# 5_Periperals.net
KiCad netlist of a schematic drawn in Altium Designer
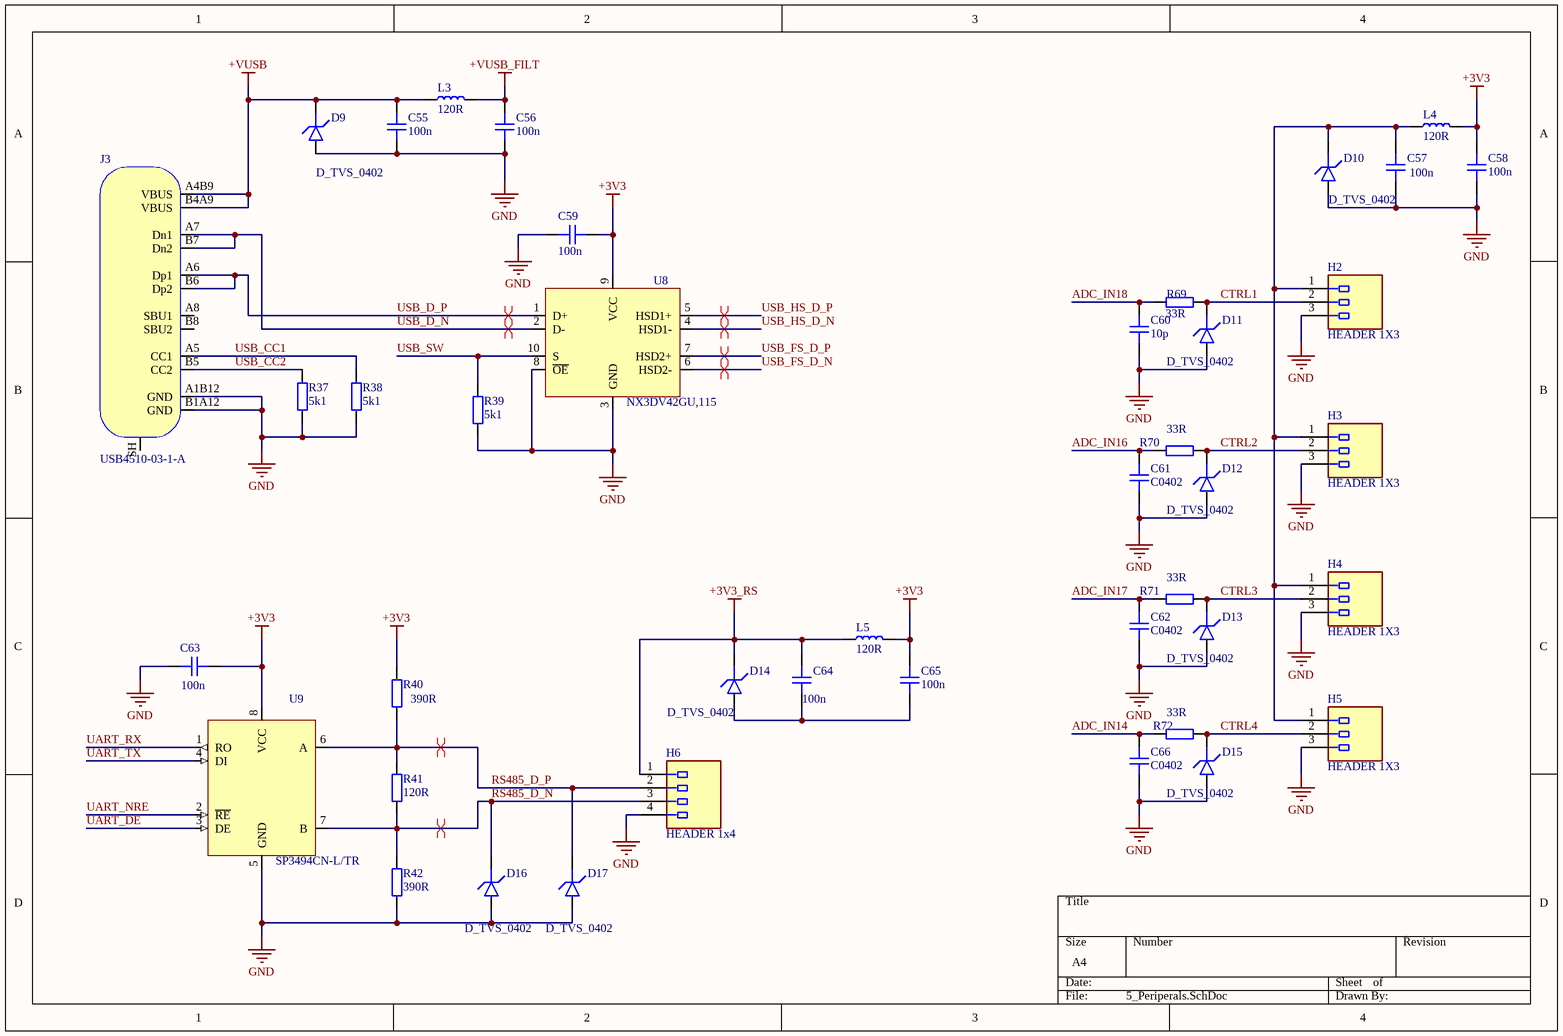
[diagram p0: 5_Periperals.SchDoc]

(export (version "E")
  (design (tool "Eeschema 10.0.6"))
  (components
    (comp (ref "C55")
      (value "100n")
      (footprint "CAP_0402")
      (description "Capacitor SMD 0402")
      (libsource (lib "Schematic-Lib-PhilsLab") (part "CAP_0402"))
    )
    (comp (ref "C56")
      (value "100n")
      (footprint "CAP_0402")
      (description "Capacitor SMD 0402")
      (libsource (lib "Schematic-Lib-PhilsLab") (part "CAP_0402"))
    )
    (comp (ref "C57")
      (value "100n")
      (footprint "CAP_0402")
      (description "Capacitor SMD 0402")
      (libsource (lib "Schematic-Lib-PhilsLab") (part "CAP_0402"))
    )
    (comp (ref "C58")
      (value "100n")
      (footprint "CAP_0402")
      (description "Capacitor SMD 0402")
      (libsource (lib "Schematic-Lib-PhilsLab") (part "CAP_0402"))
    )
    (comp (ref "C59")
      (value "100n")
      (footprint "CAP_0402")
      (description "Capacitor SMD 0402")
      (libsource (lib "Schematic-Lib-PhilsLab") (part "CAP_0402"))
    )
    (comp (ref "C60")
      (value "10p")
      (footprint "CAP_0402")
      (description "Capacitor SMD 0402")
      (libsource (lib "Schematic-Lib-PhilsLab") (part "CAP_0402"))
    )
    (comp (ref "C61")
      (value "C0402")
      (footprint "CAP_0402")
      (description "Capacitor SMD 0402")
      (libsource (lib "Schematic-Lib-PhilsLab") (part "CAP_0402"))
    )
    (comp (ref "C62")
      (value "C0402")
      (footprint "CAP_0402")
      (description "Capacitor SMD 0402")
      (libsource (lib "Schematic-Lib-PhilsLab") (part "CAP_0402"))
    )
    (comp (ref "C63")
      (value "100n")
      (footprint "CAP_0402")
      (description "Capacitor SMD 0402")
      (libsource (lib "Schematic-Lib-PhilsLab") (part "CAP_0402"))
    )
    (comp (ref "C64")
      (value "100n")
      (footprint "CAP_0402")
      (description "Capacitor SMD 0402")
      (libsource (lib "Schematic-Lib-PhilsLab") (part "CAP_0402"))
    )
    (comp (ref "C65")
      (value "100n")
      (footprint "CAP_0402")
      (description "Capacitor SMD 0402")
      (libsource (lib "Schematic-Lib-PhilsLab") (part "CAP_0402"))
    )
    (comp (ref "C66")
      (value "C0402")
      (footprint "CAP_0402")
      (description "Capacitor SMD 0402")
      (libsource (lib "Schematic-Lib-PhilsLab") (part "CAP_0402"))
    )
    (comp (ref "D9")
      (value "D_TVS_0402")
      (footprint "D_0402")
      (description "Diode TVS / ESD 0402")
      (libsource (lib "Schematic-Lib-PhilsLab") (part "D_TVS_0402"))
    )
    (comp (ref "D10")
      (value "D_TVS_0402")
      (footprint "D_0402")
      (description "Diode TVS / ESD 0402")
      (libsource (lib "Schematic-Lib-PhilsLab") (part "D_TVS_0402"))
    )
    (comp (ref "D11")
      (value "D_TVS_0402")
      (footprint "D_0402")
      (description "Diode TVS / ESD 0402")
      (libsource (lib "Schematic-Lib-PhilsLab") (part "D_TVS_0402"))
    )
    (comp (ref "D12")
      (value "D_TVS_0402")
      (footprint "D_0402")
      (description "Diode TVS / ESD 0402")
      (libsource (lib "Schematic-Lib-PhilsLab") (part "D_TVS_0402"))
    )
    (comp (ref "D13")
      (value "D_TVS_0402")
      (footprint "D_0402")
      (description "Diode TVS / ESD 0402")
      (libsource (lib "Schematic-Lib-PhilsLab") (part "D_TVS_0402"))
    )
    (comp (ref "D14")
      (value "D_TVS_0402")
      (footprint "D_0402")
      (description "Diode TVS / ESD 0402")
      (libsource (lib "Schematic-Lib-PhilsLab") (part "D_TVS_0402"))
    )
    (comp (ref "D15")
      (value "D_TVS_0402")
      (footprint "D_0402")
      (description "Diode TVS / ESD 0402")
      (libsource (lib "Schematic-Lib-PhilsLab") (part "D_TVS_0402"))
    )
    (comp (ref "D16")
      (value "D_TVS_0402")
      (footprint "D_0402")
      (description "Diode TVS / ESD 0402")
      (libsource (lib "Schematic-Lib-PhilsLab") (part "D_TVS_0402"))
    )
    (comp (ref "D17")
      (value "D_TVS_0402")
      (footprint "D_0402")
      (description "Diode TVS / ESD 0402")
      (libsource (lib "Schematic-Lib-PhilsLab") (part "D_TVS_0402"))
    )
    (comp (ref "H2")
      (value "HEADER 1X3")
      (footprint "053048-0310")
      (libsource (lib "SCHLib") (part "053048-0310"))
    )
    (comp (ref "H3")
      (value "HEADER 1X3")
      (footprint "053048-0310")
      (libsource (lib "SCHLib") (part "053048-0310"))
    )
    (comp (ref "H4")
      (value "HEADER 1X3")
      (footprint "053048-0310")
      (libsource (lib "SCHLib") (part "053048-0310"))
    )
    (comp (ref "H5")
      (value "HEADER 1X3")
      (footprint "053048-0310")
      (libsource (lib "SCHLib") (part "053048-0310"))
    )
    (comp (ref "H6")
      (value "HEADER 1x4")
      (footprint "053048-0410")
      (libsource (lib "SCHLib") (part "053048-0410"))
    )
    (comp (ref "J3")
      (value "USB4510-03-1-A")
      (footprint "USB4510-03-1-A")
      (description "USB Connector Type C SMT Mid-Mount 16 Pin")
      (fields (field (name "MANUFACTURER") "GCT"))
      (libsource (lib "Schematic-Lib-PhilsLab") (part "USB4510-03-1-A"))
    )
    (comp (ref "L3")
      (value "120R")
      (footprint "IND_0402")
      (description "Inductor SMD 0402")
      (libsource (lib "Schematic-Lib-PhilsLab") (part "IND_0402"))
    )
    (comp (ref "L4")
      (value "120R")
      (footprint "IND_0402")
      (description "Inductor SMD 0402")
      (libsource (lib "Schematic-Lib-PhilsLab") (part "IND_0402"))
    )
    (comp (ref "L5")
      (value "120R")
      (footprint "IND_0402")
      (description "Inductor SMD 0402")
      (libsource (lib "Schematic-Lib-PhilsLab") (part "IND_0402"))
    )
    (comp (ref "R37")
      (value "5k1")
      (footprint "RES_0402")
      (description "Resistor SMD 0402")
      (libsource (lib "Schematic-Lib-PhilsLab") (part "RES_0402"))
    )
    (comp (ref "R38")
      (value "5k1")
      (footprint "RES_0402")
      (description "Resistor SMD 0402")
      (libsource (lib "Schematic-Lib-PhilsLab") (part "RES_0402"))
    )
    (comp (ref "R39")
      (value "5k1")
      (footprint "RES_0402")
      (description "Resistor SMD 0402")
      (libsource (lib "Schematic-Lib-PhilsLab") (part "RES_0402"))
    )
    (comp (ref "R40")
      (value "390R")
      (footprint "RES_0402")
      (description "Resistor SMD 0402")
      (libsource (lib "Schematic-Lib-PhilsLab") (part "RES_0402"))
    )
    (comp (ref "R41")
      (value "120R")
      (footprint "RES_0402")
      (description "Resistor SMD 0402")
      (libsource (lib "Schematic-Lib-PhilsLab") (part "RES_0402"))
    )
    (comp (ref "R42")
      (value "390R")
      (footprint "RES_0402")
      (description "Resistor SMD 0402")
      (libsource (lib "Schematic-Lib-PhilsLab") (part "RES_0402"))
    )
    (comp (ref "R69")
      (value "33R")
      (footprint "RES_0402")
      (description "Resistor SMD 0402")
      (libsource (lib "Schematic-Lib-PhilsLab") (part "RES_0402"))
    )
    (comp (ref "R70")
      (value "33R")
      (footprint "RES_0402")
      (description "Resistor SMD 0402")
      (libsource (lib "Schematic-Lib-PhilsLab") (part "RES_0402"))
    )
    (comp (ref "R71")
      (value "33R")
      (footprint "RES_0402")
      (description "Resistor SMD 0402")
      (libsource (lib "Schematic-Lib-PhilsLab") (part "RES_0402"))
    )
    (comp (ref "R72")
      (value "33R")
      (footprint "RES_0402")
      (description "Resistor SMD 0402")
      (libsource (lib "Schematic-Lib-PhilsLab") (part "RES_0402"))
    )
    (comp (ref "U8")
      (value "NX3DV42GU,115")
      (footprint "XQFN-10_SOT1160-1")
      (description "USB2.0 HS DPDT Switch")
      (fields (field (name "MANUFACTURER") "NXP Semiconductors"))
      (libsource (lib "Schematic-Lib-PhilsLab") (part "NX3DV42GU,115"))
    )
    (comp (ref "U9")
      (value "SP3494CN-L/TR")
      (footprint "SOIC-8")
      (description "3.3V Low Power RS-485 / RS-422 Transceiver SOIC-8")
      (fields (field (name "MANUFACTURER") "MaxLinear"))
      (libsource (lib "Schematic-Lib-PhilsLab") (part "SP3494CN-L/TR"))
    )
  )
  (nets
    (net (code "1") (name "+3V3") (class "Default")
      (node (ref "C58") (pin "1") (pinfunction "1_1") (pintype "passive"))
      (node (ref "C59") (pin "1") (pinfunction "1_1") (pintype "passive"))
      (node (ref "C63") (pin "2") (pinfunction "2_2") (pintype "passive"))
      (node (ref "C65") (pin "1") (pinfunction "1_1") (pintype "passive"))
      (node (ref "L4") (pin "2") (pinfunction "2_2") (pintype "passive"))
      (node (ref "L5") (pin "2") (pinfunction "2_2") (pintype "passive"))
      (node (ref "R40") (pin "2") (pinfunction "2_2") (pintype "passive"))
      (node (ref "U8") (pin "9") (pinfunction "VCC_9") (pintype "passive"))
      (node (ref "U9") (pin "8") (pinfunction "VCC_8") (pintype "power_in"))
    )
    (net (code "2") (name "+3V3_RS") (class "Default")
      (node (ref "C64") (pin "1") (pinfunction "1_1") (pintype "passive"))
      (node (ref "D14") (pin "K") (pinfunction "K_K") (pintype "passive"))
      (node (ref "H6") (pin "1") (pinfunction "1_1") (pintype "passive"))
      (node (ref "L5") (pin "1") (pinfunction "1_1") (pintype "passive"))
    )
    (net (code "3") (name "+VUSB") (class "Default")
      (node (ref "C55") (pin "1") (pinfunction "1_1") (pintype "passive"))
      (node (ref "D9") (pin "K") (pinfunction "K_K") (pintype "passive"))
      (node (ref "J3") (pin "A4B9") (pinfunction "VBUS_A4B9") (pintype "passive"))
      (node (ref "J3") (pin "B4A9") (pinfunction "VBUS_B4A9") (pintype "passive"))
      (node (ref "L3") (pin "1") (pinfunction "1_1") (pintype "passive"))
    )
    (net (code "4") (name "+VUSB_FILT") (class "Default")
      (node (ref "C56") (pin "1") (pinfunction "1_1") (pintype "passive"))
      (node (ref "L3") (pin "2") (pinfunction "2_2") (pintype "passive"))
    )
    (net (code "5") (name "/ADC_IN14") (class "Default")
      (node (ref "C66") (pin "1") (pinfunction "1_1") (pintype "passive"))
      (node (ref "R72") (pin "1") (pinfunction "1_1") (pintype "passive"))
    )
    (net (code "6") (name "/ADC_IN16") (class "Default")
      (node (ref "C61") (pin "1") (pinfunction "1_1") (pintype "passive"))
      (node (ref "R70") (pin "1") (pinfunction "1_1") (pintype "passive"))
    )
    (net (code "7") (name "/ADC_IN17") (class "Default")
      (node (ref "C62") (pin "1") (pinfunction "1_1") (pintype "passive"))
      (node (ref "R71") (pin "1") (pinfunction "1_1") (pintype "passive"))
    )
    (net (code "8") (name "/ADC_IN18") (class "Default")
      (node (ref "C60") (pin "1") (pinfunction "1_1") (pintype "passive"))
      (node (ref "R69") (pin "1") (pinfunction "1_1") (pintype "passive"))
    )
    (net (code "9") (name "/CTRL1") (class "Default")
      (node (ref "D11") (pin "K") (pinfunction "K_K") (pintype "passive"))
      (node (ref "H2") (pin "2") (pinfunction "2_2") (pintype "passive"))
      (node (ref "R69") (pin "2") (pinfunction "2_2") (pintype "passive"))
    )
    (net (code "10") (name "/CTRL2") (class "Default")
      (node (ref "D12") (pin "K") (pinfunction "K_K") (pintype "passive"))
      (node (ref "H3") (pin "2") (pinfunction "2_2") (pintype "passive"))
      (node (ref "R70") (pin "2") (pinfunction "2_2") (pintype "passive"))
    )
    (net (code "11") (name "/CTRL3") (class "Default")
      (node (ref "D13") (pin "K") (pinfunction "K_K") (pintype "passive"))
      (node (ref "H4") (pin "2") (pinfunction "2_2") (pintype "passive"))
      (node (ref "R71") (pin "2") (pinfunction "2_2") (pintype "passive"))
    )
    (net (code "12") (name "/CTRL4") (class "Default")
      (node (ref "D15") (pin "K") (pinfunction "K_K") (pintype "passive"))
      (node (ref "H5") (pin "2") (pinfunction "2_2") (pintype "passive"))
      (node (ref "R72") (pin "2") (pinfunction "2_2") (pintype "passive"))
    )
    (net (code "13") (name "/RS485_D_N") (class "Default")
      (node (ref "D16") (pin "K") (pinfunction "K_K") (pintype "passive"))
      (node (ref "H6") (pin "3") (pinfunction "3_3") (pintype "passive"))
      (node (ref "R41") (pin "1") (pinfunction "1_1") (pintype "passive"))
      (node (ref "R42") (pin "2") (pinfunction "2_2") (pintype "passive"))
      (node (ref "U9") (pin "7") (pinfunction "B_7") (pintype "bidirectional"))
    )
    (net (code "14") (name "/RS485_D_P") (class "Default")
      (node (ref "D17") (pin "K") (pinfunction "K_K") (pintype "passive"))
      (node (ref "H6") (pin "2") (pinfunction "2_2") (pintype "passive"))
      (node (ref "R40") (pin "1") (pinfunction "1_1") (pintype "passive"))
      (node (ref "R41") (pin "2") (pinfunction "2_2") (pintype "passive"))
      (node (ref "U9") (pin "6") (pinfunction "A_6") (pintype "bidirectional"))
    )
    (net (code "15") (name "/UART_DE") (class "Default")
      (node (ref "U9") (pin "3") (pinfunction "DE_3") (pintype "input"))
    )
    (net (code "16") (name "/UART_NRE") (class "Default")
      (node (ref "U9") (pin "2") (pinfunction "~{RE}_2") (pintype "input"))
    )
    (net (code "17") (name "/UART_RX") (class "Default")
      (node (ref "U9") (pin "1") (pinfunction "RO_1") (pintype "output"))
    )
    (net (code "18") (name "/UART_TX") (class "Default")
      (node (ref "U9") (pin "4") (pinfunction "DI_4") (pintype "input"))
    )
    (net (code "19") (name "/USB_CC1") (class "Default")
      (node (ref "J3") (pin "A5") (pinfunction "CC1_A5") (pintype "passive"))
      (node (ref "R38") (pin "2") (pinfunction "2_2") (pintype "passive"))
    )
    (net (code "20") (name "/USB_CC2") (class "Default")
      (node (ref "J3") (pin "B5") (pinfunction "CC2_B5") (pintype "passive"))
      (node (ref "R37") (pin "2") (pinfunction "2_2") (pintype "passive"))
    )
    (net (code "21") (name "/USB_D_N") (class "Default")
      (node (ref "J3") (pin "A7") (pinfunction "Dn1_A7") (pintype "passive"))
      (node (ref "J3") (pin "B7") (pinfunction "Dn2_B7") (pintype "passive"))
      (node (ref "U8") (pin "2") (pinfunction "D-_2") (pintype "passive"))
    )
    (net (code "22") (name "/USB_D_P") (class "Default")
      (node (ref "J3") (pin "A6") (pinfunction "Dp1_A6") (pintype "passive"))
      (node (ref "J3") (pin "B6") (pinfunction "Dp2_B6") (pintype "passive"))
      (node (ref "U8") (pin "1") (pinfunction "D+_1") (pintype "passive"))
    )
    (net (code "23") (name "/USB_FS_D_N") (class "Default")
      (node (ref "U8") (pin "6") (pinfunction "HSD2-_6") (pintype "passive"))
    )
    (net (code "24") (name "/USB_FS_D_P") (class "Default")
      (node (ref "U8") (pin "7") (pinfunction "HSD2+_7") (pintype "passive"))
    )
    (net (code "25") (name "/USB_HS_D_N") (class "Default")
      (node (ref "U8") (pin "4") (pinfunction "HSD1-_4") (pintype "passive"))
    )
    (net (code "26") (name "/USB_HS_D_P") (class "Default")
      (node (ref "U8") (pin "5") (pinfunction "HSD1+_5") (pintype "passive"))
    )
    (net (code "27") (name "/USB_SW") (class "Default")
      (node (ref "R39") (pin "2") (pinfunction "2_2") (pintype "passive"))
      (node (ref "U8") (pin "10") (pinfunction "S_10") (pintype "passive"))
    )
    (net (code "28") (name "GND") (class "Default")
      (node (ref "C55") (pin "2") (pinfunction "2_2") (pintype "passive"))
      (node (ref "C56") (pin "2") (pinfunction "2_2") (pintype "passive"))
      (node (ref "C57") (pin "2") (pinfunction "2_2") (pintype "passive"))
      (node (ref "C58") (pin "2") (pinfunction "2_2") (pintype "passive"))
      (node (ref "C59") (pin "2") (pinfunction "2_2") (pintype "passive"))
      (node (ref "C60") (pin "2") (pinfunction "2_2") (pintype "passive"))
      (node (ref "C61") (pin "2") (pinfunction "2_2") (pintype "passive"))
      (node (ref "C62") (pin "2") (pinfunction "2_2") (pintype "passive"))
      (node (ref "C63") (pin "1") (pinfunction "1_1") (pintype "passive"))
      (node (ref "C66") (pin "2") (pinfunction "2_2") (pintype "passive"))
      (node (ref "D10") (pin "A") (pinfunction "A_A") (pintype "passive"))
      (node (ref "D11") (pin "A") (pinfunction "A_A") (pintype "passive"))
      (node (ref "D12") (pin "A") (pinfunction "A_A") (pintype "passive"))
      (node (ref "D13") (pin "A") (pinfunction "A_A") (pintype "passive"))
      (node (ref "D15") (pin "A") (pinfunction "A_A") (pintype "passive"))
      (node (ref "D16") (pin "A") (pinfunction "A_A") (pintype "passive"))
      (node (ref "D17") (pin "A") (pinfunction "A_A") (pintype "passive"))
      (node (ref "D9") (pin "A") (pinfunction "A_A") (pintype "passive"))
      (node (ref "H2") (pin "3") (pinfunction "3_3") (pintype "passive"))
      (node (ref "H3") (pin "3") (pinfunction "3_3") (pintype "passive"))
      (node (ref "H4") (pin "3") (pinfunction "3_3") (pintype "passive"))
      (node (ref "H5") (pin "3") (pinfunction "3_3") (pintype "passive"))
      (node (ref "H6") (pin "4") (pinfunction "4_4") (pintype "passive"))
      (node (ref "J3") (pin "A1B12") (pinfunction "GND_A1B12") (pintype "passive"))
      (node (ref "J3") (pin "B1A12") (pinfunction "GND_B1A12") (pintype "passive"))
      (node (ref "R37") (pin "1") (pinfunction "1_1") (pintype "passive"))
      (node (ref "R38") (pin "1") (pinfunction "1_1") (pintype "passive"))
      (node (ref "R39") (pin "1") (pinfunction "1_1") (pintype "passive"))
      (node (ref "R42") (pin "1") (pinfunction "1_1") (pintype "passive"))
      (node (ref "U8") (pin "3") (pinfunction "GND_3") (pintype "passive"))
      (node (ref "U8") (pin "8") (pinfunction "~{OE}_8") (pintype "passive"))
      (node (ref "U9") (pin "5") (pinfunction "GND_5") (pintype "power_in"))
    )
    (net (code "29") (name "Net-(C57-Pad1)") (class "Default")
      (node (ref "C57") (pin "1") (pinfunction "1_1") (pintype "passive"))
      (node (ref "D10") (pin "K") (pinfunction "K_K") (pintype "passive"))
      (node (ref "H2") (pin "1") (pinfunction "1_1") (pintype "passive"))
      (node (ref "H3") (pin "1") (pinfunction "1_1") (pintype "passive"))
      (node (ref "H4") (pin "1") (pinfunction "1_1") (pintype "passive"))
      (node (ref "H5") (pin "1") (pinfunction "1_1") (pintype "passive"))
      (node (ref "L4") (pin "1") (pinfunction "1_1") (pintype "passive"))
    )
    (net (code "30") (name "Net-(C64-Pad2)") (class "Default")
      (node (ref "C64") (pin "2") (pinfunction "2_2") (pintype "passive"))
      (node (ref "C65") (pin "2") (pinfunction "2_2") (pintype "passive"))
      (node (ref "D14") (pin "A") (pinfunction "A_A") (pintype "passive"))
    )
    (net (code "31") (name "unconnected-(J3-SBU1-PadA8)") (class "Default")
      (node (ref "J3") (pin "A8") (pinfunction "SBU1_A8") (pintype "passive"))
    )
    (net (code "32") (name "unconnected-(J3-SBU2-PadB8)") (class "Default")
      (node (ref "J3") (pin "B8") (pinfunction "SBU2_B8") (pintype "passive"))
    )
    (net (code "33") (name "unconnected-(J3-SHIELD-PadSH)") (class "Default")
      (node (ref "J3") (pin "SH") (pinfunction "SHIELD_SH") (pintype "passive"))
    )
  )
)
